# dosimeter.net
KiCad netlist of a schematic drawn in EAGLE
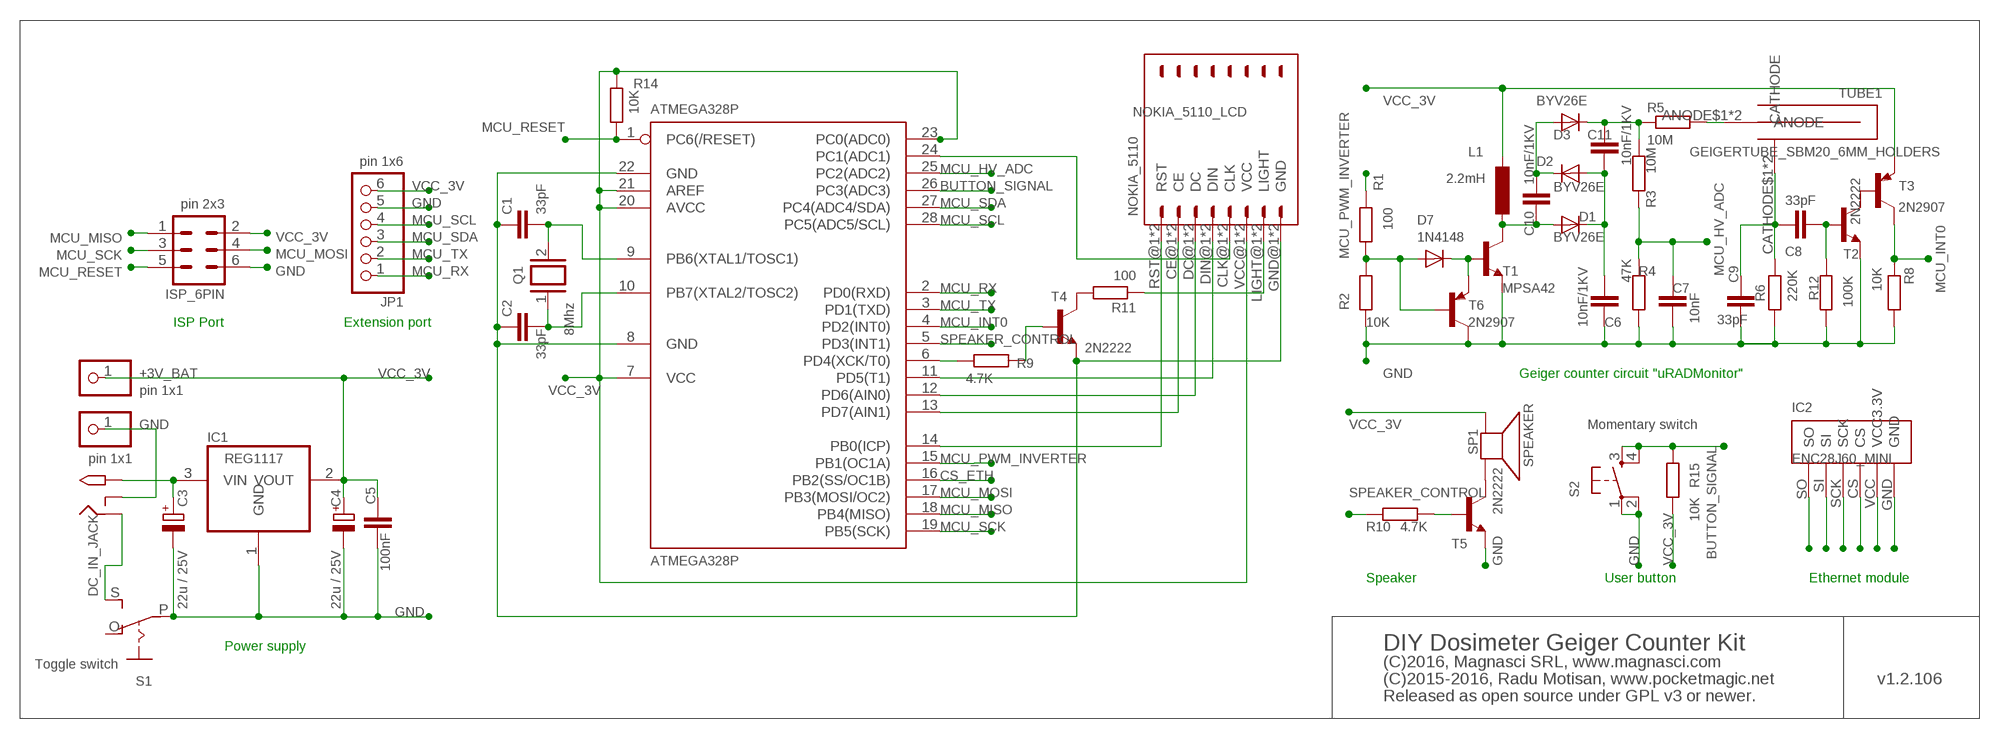
[diagram p0: schematic, sheet 1]

(export (version "E")
  (design (tool "Eeschema 10.0.6"))
  (components
    (comp (ref "+3V_BAT")
      (value "pin 1x1")
      (footprint "eagle-import:1X01")
      (libsource (lib "eagle-import") (part "PINHD-1X1"))
    )
    (comp (ref "ATMEGA328P")
      (value "ATMEGA328P")
      (footprint "eagle-import:DIL28-3")
      (libsource (lib "eagle-import") (part "MEGA8-P"))
    )
    (comp (ref "C1")
      (value "33pF")
      (footprint "eagle-import:C2.5-2")
      (libsource (lib "eagle-import") (part "C2.5/2"))
    )
    (comp (ref "C2")
      (value "33pF")
      (footprint "eagle-import:C2.5-2")
      (libsource (lib "eagle-import") (part "C2.5/2"))
    )
    (comp (ref "C3")
      (value "22u / 25V")
      (footprint "eagle-import:TT2D4L")
      (libsource (lib "eagle-import") (part "CPOL-EUTT2D4L"))
    )
    (comp (ref "C4")
      (value "22u / 25V")
      (footprint "eagle-import:TT2D4L")
      (libsource (lib "eagle-import") (part "CPOL-EUTT2D4L"))
    )
    (comp (ref "C5")
      (value "100nF")
      (footprint "eagle-import:C2.5-2")
      (libsource (lib "eagle-import") (part "C2.5/2"))
    )
    (comp (ref "C6")
      (value "10nF/1KV")
      (footprint "eagle-import:C5B3")
      (libsource (lib "eagle-import") (part "C5/3"))
    )
    (comp (ref "C7")
      (value "10nF")
      (footprint "eagle-import:C2.5-2")
      (libsource (lib "eagle-import") (part "C2.5/2"))
    )
    (comp (ref "C8")
      (value "33pF")
      (footprint "eagle-import:C2.5-2")
      (libsource (lib "eagle-import") (part "C2.5/2"))
    )
    (comp (ref "C9")
      (value "33pF")
      (footprint "eagle-import:C2.5-2")
      (libsource (lib "eagle-import") (part "C2.5/2"))
    )
    (comp (ref "C10")
      (value "10nF/1KV")
      (footprint "eagle-import:C5B3")
      (libsource (lib "eagle-import") (part "C5/3"))
    )
    (comp (ref "C11")
      (value "10nF/1KV")
      (footprint "eagle-import:C5B3")
      (libsource (lib "eagle-import") (part "C5/3"))
    )
    (comp (ref "D1")
      (value "BYV26E")
      (footprint "eagle-import:DO41-7.6")
      (libsource (lib "eagle-import") (part "DIODE-DO41-7.6"))
    )
    (comp (ref "D2")
      (value "BYV26E")
      (footprint "eagle-import:DO41-7.6")
      (libsource (lib "eagle-import") (part "DIODE-DO41-7.6"))
    )
    (comp (ref "D3")
      (value "BYV26E")
      (footprint "eagle-import:DO41-7.6")
      (libsource (lib "eagle-import") (part "DIODE-DO41-7.6"))
    )
    (comp (ref "D7")
      (value "1N4148")
      (footprint "eagle-import:D-5")
      (libsource (lib "eagle-import") (part "DIODE-D-5"))
    )
    (comp (ref "DC_IN_JACK")
      (value "DC IN JACK")
      (footprint "eagle-import:PJ-102A")
      (libsource (lib "eagle-import") (part "2.1MMJACKTHM"))
    )
    (comp (ref "GND")
      (value "pin 1x1")
      (footprint "eagle-import:1X01")
      (libsource (lib "eagle-import") (part "PINHD-1X1"))
    )
    (comp (ref "IC1")
      (value "REG1117")
      (footprint "eagle-import:SOT223")
      (libsource (lib "eagle-import") (part "REG1117"))
    )
    (comp (ref "IC2")
      (value "ENC28J60_MINI")
      (footprint "eagle-import:ENC28J60_MINI")
      (libsource (lib "eagle-import") (part "ENC28J60_MINI"))
    )
    (comp (ref "ISP_6PIN")
      (value "pin 2x3")
      (footprint "eagle-import:MA03-2")
      (libsource (lib "eagle-import") (part "MA03-2"))
    )
    (comp (ref "JP1")
      (value "pin 1x6")
      (footprint "eagle-import:1X06-CLEAN")
      (libsource (lib "eagle-import") (part "PINHD-1X6CLEAN"))
    )
    (comp (ref "L1")
      (value "2.2mH")
      (footprint "eagle-import:0207_10")
      (libsource (lib "eagle-import") (part "L-EU0207/10"))
    )
    (comp (ref "NOKIA_5110")
      (value "NOKIA_5110_LCD")
      (footprint "eagle-import:NOKIA5110")
      (libsource (lib "eagle-import") (part "NOKIA5110"))
    )
    (comp (ref "Q1")
      (value "8Mhz")
      (footprint "eagle-import:QS")
      (libsource (lib "eagle-import") (part "XTAL/S"))
    )
    (comp (ref "R1")
      (value "100")
      (footprint "eagle-import:0204_7")
      (libsource (lib "eagle-import") (part "R-EU_0204/7"))
    )
    (comp (ref "R2")
      (value "10K")
      (footprint "eagle-import:0204_7")
      (libsource (lib "eagle-import") (part "R-EU_0204/7"))
    )
    (comp (ref "R3")
      (value "10M")
      (footprint "eagle-import:0204_7")
      (libsource (lib "eagle-import") (part "R-EU_0204/7"))
    )
    (comp (ref "R4")
      (value "47K")
      (footprint "eagle-import:0204_7")
      (libsource (lib "eagle-import") (part "R-EU_0204/7"))
    )
    (comp (ref "R5")
      (value "10M")
      (footprint "eagle-import:0204_7")
      (libsource (lib "eagle-import") (part "R-EU_0204/7"))
    )
    (comp (ref "R6")
      (value "220K")
      (footprint "eagle-import:0204_7")
      (libsource (lib "eagle-import") (part "R-EU_0204/7"))
    )
    (comp (ref "R8")
      (value "10K")
      (footprint "eagle-import:0204_7")
      (libsource (lib "eagle-import") (part "R-EU_0204/7"))
    )
    (comp (ref "R9")
      (value "4.7K")
      (footprint "eagle-import:0204_7")
      (libsource (lib "eagle-import") (part "R-EU_0204/7"))
    )
    (comp (ref "R10")
      (value "4.7K")
      (footprint "eagle-import:0204_7")
      (libsource (lib "eagle-import") (part "R-EU_0204/7"))
    )
    (comp (ref "R11")
      (value "100")
      (footprint "eagle-import:0204_7")
      (libsource (lib "eagle-import") (part "R-EU_0204/7"))
    )
    (comp (ref "R12")
      (value "100K")
      (footprint "eagle-import:0204_7")
      (libsource (lib "eagle-import") (part "R-EU_0204/7"))
    )
    (comp (ref "R14")
      (value "10K")
      (footprint "eagle-import:0204_7")
      (libsource (lib "eagle-import") (part "R-EU_0204/7"))
    )
    (comp (ref "R15")
      (value "10K")
      (footprint "eagle-import:0204_7")
      (libsource (lib "eagle-import") (part "R-EU_0204/7"))
    )
    (comp (ref "S1")
      (value "Toggle switch")
      (footprint "eagle-import:EG1218")
      (libsource (lib "eagle-import") (part "EG1218S"))
    )
    (comp (ref "S2")
      (value "Momentary switch")
      (footprint "eagle-import:TACTILE-PTH")
      (libsource (lib "eagle-import") (part "TAC_SWITCHPTH"))
    )
    (comp (ref "SP1")
      (value "SPEAKER")
      (footprint "eagle-import:AL60P")
      (libsource (lib "eagle-import") (part "SPEAKER/AL60P"))
    )
    (comp (ref "T1")
      (value "MPSA42")
      (footprint "eagle-import:TO92-EBC-OVAL")
      (libsource (lib "eagle-import") (part "2N2222"))
    )
    (comp (ref "T2")
      (value "2N2222")
      (footprint "eagle-import:TO92-EBC")
      (libsource (lib "eagle-import") (part "-NPN-TO92-EBC2N2222"))
    )
    (comp (ref "T3")
      (value "2N2907")
      (footprint "eagle-import:TO92-EBC-OVAL")
      (libsource (lib "eagle-import") (part "2N2907"))
    )
    (comp (ref "T4")
      (value "2N2222")
      (footprint "eagle-import:TO92-EBC")
      (libsource (lib "eagle-import") (part "-NPN-TO92-EBC2N2222"))
    )
    (comp (ref "T5")
      (value "2N2222")
      (footprint "eagle-import:TO92-EBC")
      (libsource (lib "eagle-import") (part "-NPN-TO92-EBC2N2222"))
    )
    (comp (ref "T6")
      (value "2N2907")
      (footprint "eagle-import:TO92-EBC-OVAL")
      (libsource (lib "eagle-import") (part "2N2907"))
    )
    (comp (ref "TUBE1")
      (value "GEIGERTUBE_SBM20_6MM_HOLDERS")
      (footprint "eagle-import:GEIGERTUBE_SBM20_6MM_HOLDERS")
      (libsource (lib "eagle-import") (part "GEIGERTUBE_SBM20_6MM_HOLDERS"))
    )
  )
  (nets
    (net (code "1") (name "BUTTON_SIGNAL") (class "Default")
      (node (ref "ATMEGA328P") (pin "26") (pinfunction "PC3(ADC3)_26") (pintype "bidirectional"))
      (node (ref "R15") (pin "1") (pinfunction "1_1") (pintype "passive"))
      (node (ref "S2") (pin "3") (pinfunction "3_3") (pintype "passive"))
      (node (ref "S2") (pin "4") (pinfunction "4_4") (pintype "passive"))
    )
    (net (code "2") (name "CS_ETH") (class "Default")
      (node (ref "ATMEGA328P") (pin "16") (pinfunction "PB2(SS/OC1B)_16") (pintype "bidirectional"))
      (node (ref "IC2") (pin "CS") (pinfunction "CS_CS") (pintype "bidirectional"))
    )
    (net (code "3") (name "GND") (class "Default")
      (node (ref "ATMEGA328P") (pin "22") (pinfunction "GND_22") (pintype "power_in"))
      (node (ref "ATMEGA328P") (pin "8") (pinfunction "GND_8") (pintype "power_in"))
      (node (ref "C1") (pin "1") (pinfunction "1_1") (pintype "passive"))
      (node (ref "C2") (pin "1") (pinfunction "1_1") (pintype "passive"))
      (node (ref "C3") (pin "-") (pinfunction "-_-") (pintype "passive"))
      (node (ref "C4") (pin "-") (pinfunction "-_-") (pintype "passive"))
      (node (ref "C5") (pin "1") (pinfunction "1_1") (pintype "passive"))
      (node (ref "C6") (pin "2") (pinfunction "2_2") (pintype "passive"))
      (node (ref "C7") (pin "1") (pinfunction "1_1") (pintype "passive"))
      (node (ref "C9") (pin "2") (pinfunction "2_2") (pintype "passive"))
      (node (ref "IC1") (pin "1") (pinfunction "GND_1") (pintype "power_in"))
      (node (ref "IC2") (pin "GND") (pinfunction "GND_GND") (pintype "bidirectional"))
      (node (ref "ISP_6PIN") (pin "6") (pinfunction "6_6") (pintype "passive"))
      (node (ref "JP1") (pin "5") (pinfunction "5_5") (pintype "passive"))
      (node (ref "NOKIA_5110") (pin "GND@1") (pinfunction "GND_GND@1") (pintype "bidirectional"))
      (node (ref "NOKIA_5110") (pin "GND@2") (pinfunction "GND_GND@2") (pintype "bidirectional"))
      (node (ref "R12") (pin "2") (pinfunction "2_2") (pintype "passive"))
      (node (ref "R2") (pin "1") (pinfunction "1_1") (pintype "passive"))
      (node (ref "R4") (pin "2") (pinfunction "2_2") (pintype "passive"))
      (node (ref "R6") (pin "1") (pinfunction "1_1") (pintype "passive"))
      (node (ref "R8") (pin "2") (pinfunction "2_2") (pintype "passive"))
      (node (ref "S1") (pin "P") (pinfunction "P_P") (pintype "passive"))
      (node (ref "S2") (pin "1") (pinfunction "1_1") (pintype "passive"))
      (node (ref "S2") (pin "2") (pinfunction "2_2") (pintype "passive"))
      (node (ref "T1") (pin "E") (pinfunction "E_E") (pintype "passive"))
      (node (ref "T2") (pin "E") (pinfunction "E_E") (pintype "passive"))
      (node (ref "T4") (pin "E") (pinfunction "E_E") (pintype "passive"))
      (node (ref "T5") (pin "E") (pinfunction "E_E") (pintype "passive"))
      (node (ref "T6") (pin "C") (pinfunction "C_C") (pintype "passive"))
    )
    (net (code "4") (name "MCU_HV_ADC") (class "Default")
      (node (ref "ATMEGA328P") (pin "25") (pinfunction "PC2(ADC2)_25") (pintype "bidirectional"))
      (node (ref "C7") (pin "2") (pinfunction "2_2") (pintype "passive"))
      (node (ref "R3") (pin "1") (pinfunction "1_1") (pintype "passive"))
      (node (ref "R4") (pin "1") (pinfunction "1_1") (pintype "passive"))
    )
    (net (code "5") (name "MCU_INT0") (class "Default")
      (node (ref "ATMEGA328P") (pin "4") (pinfunction "PD2(INT0)_4") (pintype "bidirectional"))
      (node (ref "R8") (pin "1") (pinfunction "1_1") (pintype "passive"))
      (node (ref "T3") (pin "C") (pinfunction "C_C") (pintype "passive"))
    )
    (net (code "6") (name "MCU_MISO") (class "Default")
      (node (ref "ATMEGA328P") (pin "18") (pinfunction "PB4(MISO)_18") (pintype "bidirectional"))
      (node (ref "IC2") (pin "SO") (pinfunction "SO_SO") (pintype "bidirectional"))
      (node (ref "ISP_6PIN") (pin "1") (pinfunction "1_1") (pintype "passive"))
    )
    (net (code "7") (name "MCU_MOSI") (class "Default")
      (node (ref "ATMEGA328P") (pin "17") (pinfunction "PB3(MOSI/OC2)_17") (pintype "bidirectional"))
      (node (ref "IC2") (pin "SI") (pinfunction "SI_SI") (pintype "bidirectional"))
      (node (ref "ISP_6PIN") (pin "4") (pinfunction "4_4") (pintype "passive"))
    )
    (net (code "8") (name "MCU_PWM_INVERTER") (class "Default")
      (node (ref "ATMEGA328P") (pin "15") (pinfunction "PB1(OC1A)_15") (pintype "bidirectional"))
      (node (ref "R1") (pin "1") (pinfunction "1_1") (pintype "passive"))
    )
    (net (code "9") (name "MCU_RESET") (class "Default")
      (node (ref "ATMEGA328P") (pin "1") (pinfunction "PC6(/RESET)_1") (pintype "bidirectional"))
      (node (ref "ISP_6PIN") (pin "5") (pinfunction "5_5") (pintype "passive"))
      (node (ref "R14") (pin "1") (pinfunction "1_1") (pintype "passive"))
    )
    (net (code "10") (name "MCU_RX") (class "Default")
      (node (ref "ATMEGA328P") (pin "2") (pinfunction "PD0(RXD)_2") (pintype "bidirectional"))
      (node (ref "JP1") (pin "1") (pinfunction "1_1") (pintype "passive"))
    )
    (net (code "11") (name "MCU_SCK") (class "Default")
      (node (ref "ATMEGA328P") (pin "19") (pinfunction "PB5(SCK)_19") (pintype "bidirectional"))
      (node (ref "IC2") (pin "SCK") (pinfunction "SCK_SCK") (pintype "bidirectional"))
      (node (ref "ISP_6PIN") (pin "3") (pinfunction "3_3") (pintype "passive"))
    )
    (net (code "12") (name "MCU_SCL") (class "Default")
      (node (ref "ATMEGA328P") (pin "28") (pinfunction "PC5(ADC5/SCL)_28") (pintype "bidirectional"))
      (node (ref "JP1") (pin "4") (pinfunction "4_4") (pintype "passive"))
    )
    (net (code "13") (name "MCU_SDA") (class "Default")
      (node (ref "ATMEGA328P") (pin "27") (pinfunction "PC4(ADC4/SDA)_27") (pintype "bidirectional"))
      (node (ref "JP1") (pin "3") (pinfunction "3_3") (pintype "passive"))
    )
    (net (code "14") (name "MCU_TX") (class "Default")
      (node (ref "ATMEGA328P") (pin "3") (pinfunction "PD1(TXD)_3") (pintype "bidirectional"))
      (node (ref "JP1") (pin "2") (pinfunction "2_2") (pintype "passive"))
    )
    (net (code "15") (name "N$27") (class "Default")
      (node (ref "D7") (pin "A") (pinfunction "A_A") (pintype "passive"))
      (node (ref "R1") (pin "2") (pinfunction "2_2") (pintype "passive"))
      (node (ref "R2") (pin "2") (pinfunction "2_2") (pintype "passive"))
      (node (ref "T6") (pin "B") (pinfunction "B_B") (pintype "passive"))
    )
    (net (code "16") (name "Net-(ATMEGA328P-PB0(ICP))") (class "Default")
      (node (ref "ATMEGA328P") (pin "14") (pinfunction "PB0(ICP)_14") (pintype "bidirectional"))
      (node (ref "NOKIA_5110") (pin "RST@1") (pinfunction "RST_RST@1") (pintype "bidirectional"))
      (node (ref "NOKIA_5110") (pin "RST@2") (pinfunction "RST_RST@2") (pintype "bidirectional"))
    )
    (net (code "17") (name "Net-(ATMEGA328P-PB6(XTAL1{slash}TOSC1))") (class "Default")
      (node (ref "ATMEGA328P") (pin "9") (pinfunction "PB6(XTAL1/TOSC1)_9") (pintype "bidirectional"))
      (node (ref "C1") (pin "2") (pinfunction "2_2") (pintype "passive"))
      (node (ref "Q1") (pin "2") (pinfunction "2_2") (pintype "passive"))
    )
    (net (code "18") (name "Net-(ATMEGA328P-PB7(XTAL2{slash}TOSC2))") (class "Default")
      (node (ref "ATMEGA328P") (pin "10") (pinfunction "PB7(XTAL2/TOSC2)_10") (pintype "bidirectional"))
      (node (ref "C2") (pin "2") (pinfunction "2_2") (pintype "passive"))
      (node (ref "Q1") (pin "1") (pinfunction "1_1") (pintype "passive"))
    )
    (net (code "19") (name "Net-(ATMEGA328P-PC1(ADC1))") (class "Default")
      (node (ref "ATMEGA328P") (pin "24") (pinfunction "PC1(ADC1)_24") (pintype "bidirectional"))
      (node (ref "NOKIA_5110") (pin "CLK@1") (pinfunction "CLK_CLK@1") (pintype "bidirectional"))
      (node (ref "NOKIA_5110") (pin "CLK@2") (pinfunction "CLK_CLK@2") (pintype "bidirectional"))
    )
    (net (code "20") (name "Net-(ATMEGA328P-PD4(XCK{slash}T0))") (class "Default")
      (node (ref "ATMEGA328P") (pin "6") (pinfunction "PD4(XCK/T0)_6") (pintype "bidirectional"))
      (node (ref "R9") (pin "1") (pinfunction "1_1") (pintype "passive"))
    )
    (net (code "21") (name "Net-(ATMEGA328P-PD5(T1))") (class "Default")
      (node (ref "ATMEGA328P") (pin "11") (pinfunction "PD5(T1)_11") (pintype "bidirectional"))
      (node (ref "NOKIA_5110") (pin "DIN@1") (pinfunction "DIN_DIN@1") (pintype "bidirectional"))
      (node (ref "NOKIA_5110") (pin "DIN@2") (pinfunction "DIN_DIN@2") (pintype "bidirectional"))
    )
    (net (code "22") (name "Net-(ATMEGA328P-PD6(AIN0))") (class "Default")
      (node (ref "ATMEGA328P") (pin "12") (pinfunction "PD6(AIN0)_12") (pintype "bidirectional"))
      (node (ref "NOKIA_5110") (pin "DC@1") (pinfunction "DC_DC@1") (pintype "bidirectional"))
      (node (ref "NOKIA_5110") (pin "DC@2") (pinfunction "DC_DC@2") (pintype "bidirectional"))
    )
    (net (code "23") (name "Net-(ATMEGA328P-PD7(AIN1))") (class "Default")
      (node (ref "ATMEGA328P") (pin "13") (pinfunction "PD7(AIN1)_13") (pintype "bidirectional"))
      (node (ref "NOKIA_5110") (pin "CE@1") (pinfunction "CE_CE@1") (pintype "bidirectional"))
      (node (ref "NOKIA_5110") (pin "CE@2") (pinfunction "CE_CE@2") (pintype "bidirectional"))
    )
    (net (code "24") (name "Net-(C8-Pad1)") (class "Default")
      (node (ref "C8") (pin "1") (pinfunction "1_1") (pintype "passive"))
      (node (ref "R12") (pin "1") (pinfunction "1_1") (pintype "passive"))
      (node (ref "T2") (pin "B") (pinfunction "B_B") (pintype "passive"))
    )
    (net (code "25") (name "Net-(C8-Pad2)") (class "Default")
      (node (ref "C8") (pin "2") (pinfunction "2_2") (pintype "passive"))
      (node (ref "C9") (pin "1") (pinfunction "1_1") (pintype "passive"))
      (node (ref "R6") (pin "2") (pinfunction "2_2") (pintype "passive"))
      (node (ref "TUBE1") (pin "CATHODE$1") (pinfunction "CATHODE_CATHODE$1") (pintype "bidirectional"))
      (node (ref "TUBE1") (pin "CATHODE$2") (pinfunction "CATHODE_CATHODE$2") (pintype "bidirectional"))
    )
    (net (code "26") (name "Net-(C10-Pad1)") (class "Default")
      (node (ref "C10") (pin "1") (pinfunction "1_1") (pintype "passive"))
      (node (ref "D2") (pin "C") (pinfunction "C_C") (pintype "passive"))
      (node (ref "D3") (pin "A") (pinfunction "A_A") (pintype "passive"))
    )
    (net (code "27") (name "Net-(C10-Pad2)") (class "Default")
      (node (ref "C10") (pin "2") (pinfunction "2_2") (pintype "passive"))
      (node (ref "D1") (pin "A") (pinfunction "A_A") (pintype "passive"))
      (node (ref "L1") (pin "2") (pinfunction "2_2") (pintype "passive"))
      (node (ref "T1") (pin "C") (pinfunction "C_C") (pintype "passive"))
    )
    (net (code "28") (name "Net-(C11-Pad1)") (class "Default")
      (node (ref "C11") (pin "1") (pinfunction "1_1") (pintype "passive"))
      (node (ref "D3") (pin "C") (pinfunction "C_C") (pintype "passive"))
      (node (ref "R3") (pin "2") (pinfunction "2_2") (pintype "passive"))
      (node (ref "R5") (pin "1") (pinfunction "1_1") (pintype "passive"))
    )
    (net (code "29") (name "Net-(C11-Pad2)") (class "Default")
      (node (ref "C11") (pin "2") (pinfunction "2_2") (pintype "passive"))
      (node (ref "C6") (pin "1") (pinfunction "1_1") (pintype "passive"))
      (node (ref "D1") (pin "C") (pinfunction "C_C") (pintype "passive"))
      (node (ref "D2") (pin "A") (pinfunction "A_A") (pintype "passive"))
    )
    (net (code "30") (name "Net-(D7-PadC)") (class "Default")
      (node (ref "D7") (pin "C") (pinfunction "C_C") (pintype "passive"))
      (node (ref "T1") (pin "B") (pinfunction "B_B") (pintype "passive"))
      (node (ref "T6") (pin "E") (pinfunction "E_E") (pintype "passive"))
    )
    (net (code "31") (name "Net-(DC_IN_JACK-PadRING)") (class "Default")
      (node (ref "DC_IN_JACK") (pin "RING") (pinfunction "RING_RING") (pintype "bidirectional"))
      (node (ref "S1") (pin "S") (pinfunction "S_S") (pintype "passive"))
    )
    (net (code "32") (name "Net-(DC_IN_JACK-PadRING_SW)") (class "Default")
      (node (ref "DC_IN_JACK") (pin "RING_SW") (pinfunction "RING_SW_RING_SW") (pintype "bidirectional"))
      (node (ref "GND") (pin "1") (pinfunction "1_1") (pintype "passive"))
    )
    (net (code "33") (name "Net-(IC1-VIN)") (class "Default")
      (node (ref "C3") (pin "+") (pinfunction "+_+") (pintype "passive"))
      (node (ref "DC_IN_JACK") (pin "TIP") (pinfunction "TIP_TIP") (pintype "bidirectional"))
      (node (ref "IC1") (pin "3") (pinfunction "VIN_3") (pintype "input"))
    )
    (net (code "34") (name "Net-(NOKIA_5110-LIGHT-PadLIGHT@1)") (class "Default")
      (node (ref "NOKIA_5110") (pin "LIGHT@1") (pinfunction "LIGHT_LIGHT@1") (pintype "bidirectional"))
      (node (ref "NOKIA_5110") (pin "LIGHT@2") (pinfunction "LIGHT_LIGHT@2") (pintype "bidirectional"))
      (node (ref "R11") (pin "1") (pinfunction "1_1") (pintype "passive"))
    )
    (net (code "35") (name "Net-(R5-Pad2)") (class "Default")
      (node (ref "R5") (pin "2") (pinfunction "2_2") (pintype "passive"))
      (node (ref "TUBE1") (pin "ANODE$1") (pinfunction "ANODE_ANODE$1") (pintype "bidirectional"))
      (node (ref "TUBE1") (pin "ANODE$2") (pinfunction "ANODE_ANODE$2") (pintype "bidirectional"))
    )
    (net (code "36") (name "Net-(R9-Pad2)") (class "Default")
      (node (ref "R9") (pin "2") (pinfunction "2_2") (pintype "passive"))
      (node (ref "T4") (pin "B") (pinfunction "B_B") (pintype "passive"))
    )
    (net (code "37") (name "Net-(R10-Pad2)") (class "Default")
      (node (ref "R10") (pin "2") (pinfunction "2_2") (pintype "passive"))
      (node (ref "T5") (pin "B") (pinfunction "B_B") (pintype "passive"))
    )
    (net (code "38") (name "Net-(R11-Pad2)") (class "Default")
      (node (ref "R11") (pin "2") (pinfunction "2_2") (pintype "passive"))
      (node (ref "T4") (pin "C") (pinfunction "C_C") (pintype "passive"))
    )
    (net (code "39") (name "Net-(SP1--)") (class "Default")
      (node (ref "SP1") (pin "2") (pinfunction "-_2") (pintype "passive"))
      (node (ref "T5") (pin "C") (pinfunction "C_C") (pintype "passive"))
    )
    (net (code "40") (name "Net-(T2-PadC)") (class "Default")
      (node (ref "T2") (pin "C") (pinfunction "C_C") (pintype "passive"))
      (node (ref "T3") (pin "B") (pinfunction "B_B") (pintype "passive"))
    )
    (net (code "41") (name "SPEAKER_CONTROL") (class "Default")
      (node (ref "ATMEGA328P") (pin "5") (pinfunction "PD3(INT1)_5") (pintype "bidirectional"))
      (node (ref "R10") (pin "1") (pinfunction "1_1") (pintype "passive"))
    )
    (net (code "42") (name "VCC_3V") (class "Default")
      (node (ref "+3V_BAT") (pin "1") (pinfunction "1_1") (pintype "passive"))
      (node (ref "ATMEGA328P") (pin "20") (pinfunction "AVCC_20") (pintype "power_in"))
      (node (ref "ATMEGA328P") (pin "21") (pinfunction "AREF_21") (pintype "passive"))
      (node (ref "ATMEGA328P") (pin "23") (pinfunction "PC0(ADC0)_23") (pintype "bidirectional"))
      (node (ref "ATMEGA328P") (pin "7") (pinfunction "VCC_7") (pintype "power_in"))
      (node (ref "C4") (pin "+") (pinfunction "+_+") (pintype "passive"))
      (node (ref "C5") (pin "2") (pinfunction "2_2") (pintype "passive"))
      (node (ref "IC1") (pin "2") (pinfunction "VOUT_2") (pintype "output"))
      (node (ref "IC2") (pin "VCC") (pinfunction "VCC3.3V_VCC") (pintype "bidirectional"))
      (node (ref "ISP_6PIN") (pin "2") (pinfunction "2_2") (pintype "passive"))
      (node (ref "JP1") (pin "6") (pinfunction "6_6") (pintype "passive"))
      (node (ref "L1") (pin "1") (pinfunction "1_1") (pintype "passive"))
      (node (ref "NOKIA_5110") (pin "VCC@1") (pinfunction "VCC_VCC@1") (pintype "bidirectional"))
      (node (ref "NOKIA_5110") (pin "VCC@2") (pinfunction "VCC_VCC@2") (pintype "bidirectional"))
      (node (ref "R14") (pin "2") (pinfunction "2_2") (pintype "passive"))
      (node (ref "R15") (pin "2") (pinfunction "2_2") (pintype "passive"))
      (node (ref "SP1") (pin "1") (pinfunction "+_1") (pintype "passive"))
      (node (ref "T3") (pin "E") (pinfunction "E_E") (pintype "passive"))
    )
    (net (code "43") (name "unconnected-(S1-PadO)") (class "Default")
      (node (ref "S1") (pin "O") (pinfunction "O_O") (pintype "passive"))
    )
  )
)
